# IWRL6432.net
KiCad netlist of a schematic drawn in Altium Designer
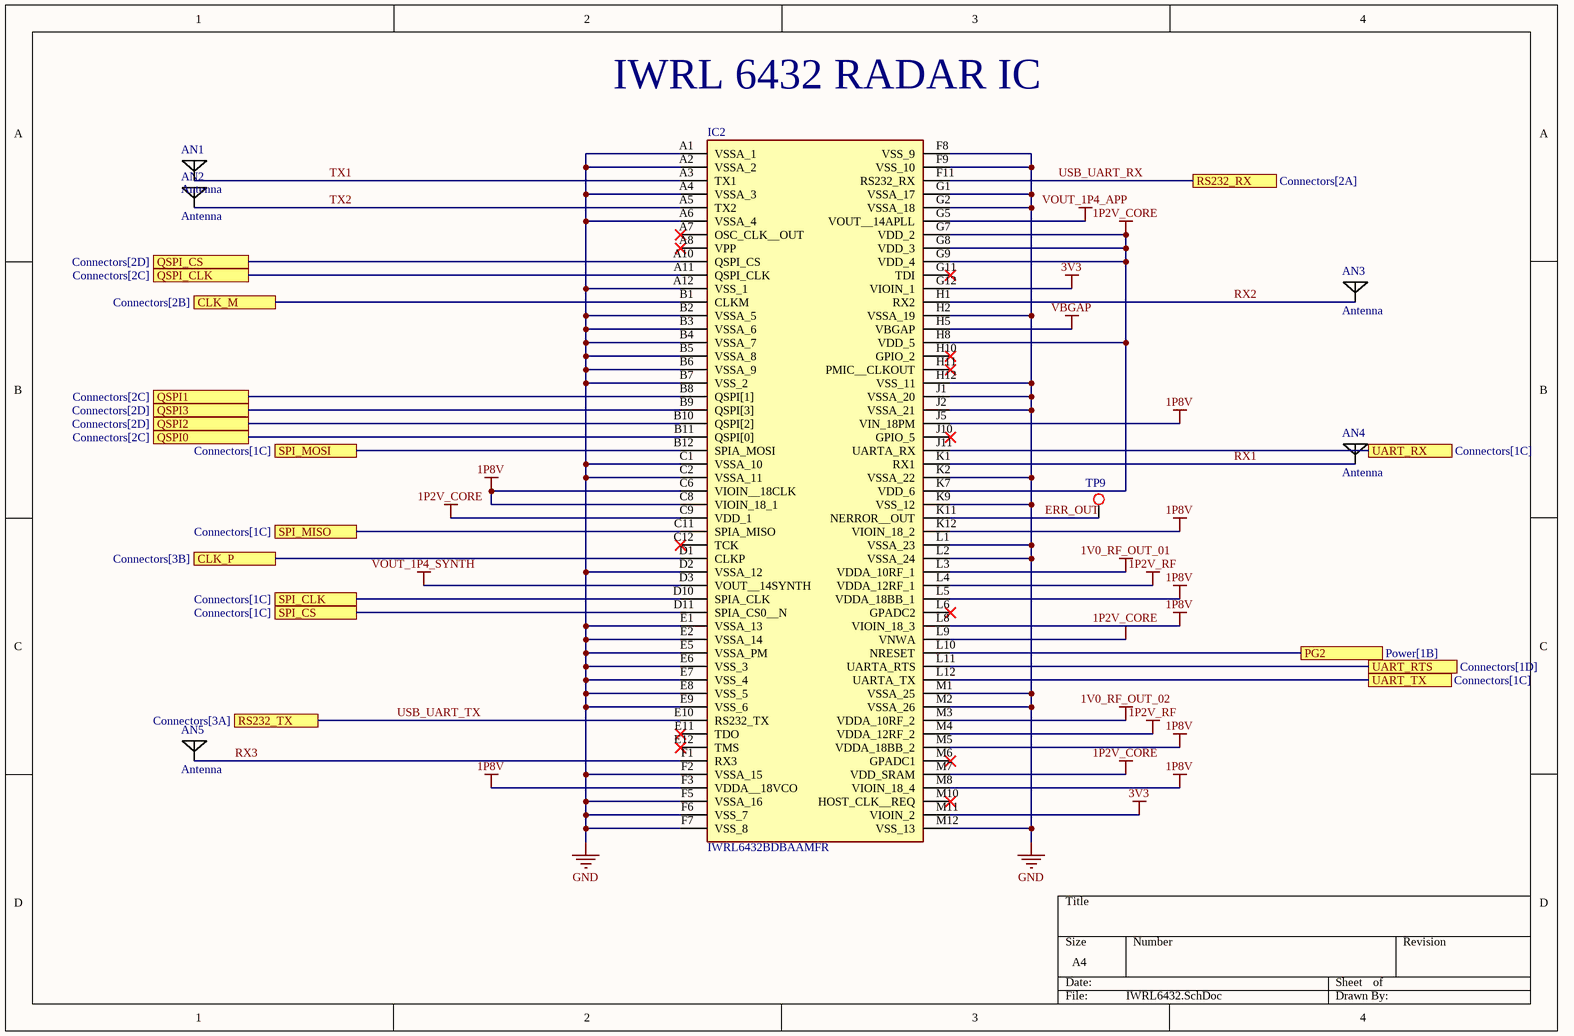
[diagram p0: IWRL6432.SchDoc]

(export (version "E")
  (design (tool "Eeschema 10.0.6"))
  (components
    (comp (ref "AN1") (value "Antenna") (footprint "Antenna") (libsource (lib "Schlib1") (part "Antenna")))
    (comp (ref "AN2") (value "Antenna") (footprint "Antenna") (libsource (lib "Schlib1") (part "Antenna")))
    (comp (ref "AN3") (value "Antenna") (footprint "Antenna") (libsource (lib "Schlib1") (part "Antenna")))
    (comp (ref "AN4") (value "Antenna") (footprint "Antenna") (libsource (lib "Schlib1") (part "Antenna")))
    (comp (ref "AN5") (value "Antenna") (footprint "Antenna") (libsource (lib "Schlib1") (part "Antenna")))
    (comp (ref "IC2")
      (value "IWRL6432BDBAAMFR")
      (footprint "SamacSys:BGA102C50P12X12_645X645X97")
      (description "Integrated Circuit")
      (libsource (lib "*") (part "IWRL6432BDBAAMFR"))
    )
    (comp (ref "TP9") (value "TP_1") (footprint "Testpoint") (libsource (lib "Schlib1") (part "Testpoint")))
  )
  (nets
    (net (code "1") (name "/CLK_M") (class "Default")
      (node (ref "IC2") (pin "B1") (pinfunction "CLKM_B1") (pintype "passive"))
    )
    (net (code "2") (name "/CLK_P") (class "Default")
      (node (ref "IC2") (pin "D1") (pinfunction "CLKP_D1") (pintype "passive"))
    )
    (net (code "3") (name "/ERR_OUT") (class "Default")
      (node (ref "IC2") (pin "K11") (pinfunction "NERROR__OUT_K11") (pintype "passive"))
      (node (ref "TP9") (pin "0") (pinfunction "0_0") (pintype "passive"))
    )
    (net (code "4") (name "/PG2") (class "Default")
      (node (ref "IC2") (pin "L10") (pinfunction "NRESET_L10") (pintype "passive"))
    )
    (net (code "5") (name "/QSPI0") (class "Default")
      (node (ref "IC2") (pin "B11") (pinfunction "QSPI[0]_B11") (pintype "passive"))
    )
    (net (code "6") (name "/QSPI1") (class "Default")
      (node (ref "IC2") (pin "B8") (pinfunction "QSPI[1]_B8") (pintype "passive"))
    )
    (net (code "7") (name "/QSPI2") (class "Default")
      (node (ref "IC2") (pin "B10") (pinfunction "QSPI[2]_B10") (pintype "passive"))
    )
    (net (code "8") (name "/QSPI3") (class "Default")
      (node (ref "IC2") (pin "B9") (pinfunction "QSPI[3]_B9") (pintype "passive"))
    )
    (net (code "9") (name "/QSPI_CLK") (class "Default")
      (node (ref "IC2") (pin "A11") (pinfunction "QSPI_CLK_A11") (pintype "passive"))
    )
    (net (code "10") (name "/QSPI_CS") (class "Default")
      (node (ref "IC2") (pin "A10") (pinfunction "QSPI_CS_A10") (pintype "passive"))
    )
    (net (code "11") (name "/RX1") (class "Default")
      (node (ref "AN4") (pin "0") (pinfunction "0_0") (pintype "passive"))
      (node (ref "IC2") (pin "K1") (pinfunction "RX1_K1") (pintype "passive"))
    )
    (net (code "12") (name "/RX2") (class "Default")
      (node (ref "AN3") (pin "0") (pinfunction "0_0") (pintype "passive"))
      (node (ref "IC2") (pin "H1") (pinfunction "RX2_H1") (pintype "passive"))
    )
    (net (code "13") (name "/RX3") (class "Default")
      (node (ref "AN5") (pin "0") (pinfunction "0_0") (pintype "passive"))
      (node (ref "IC2") (pin "F1") (pinfunction "RX3_F1") (pintype "passive"))
    )
    (net (code "14") (name "/SPI_CLK") (class "Default")
      (node (ref "IC2") (pin "D10") (pinfunction "SPIA_CLK_D10") (pintype "passive"))
    )
    (net (code "15") (name "/SPI_CS") (class "Default")
      (node (ref "IC2") (pin "D11") (pinfunction "SPIA_CS0__N_D11") (pintype "passive"))
    )
    (net (code "16") (name "/SPI_MISO") (class "Default")
      (node (ref "IC2") (pin "C11") (pinfunction "SPIA_MISO_C11") (pintype "passive"))
    )
    (net (code "17") (name "/SPI_MOSI") (class "Default")
      (node (ref "IC2") (pin "B12") (pinfunction "SPIA_MOSI_B12") (pintype "passive"))
    )
    (net (code "18") (name "/TX1") (class "Default")
      (node (ref "AN1") (pin "0") (pinfunction "0_0") (pintype "passive"))
      (node (ref "IC2") (pin "A3") (pinfunction "TX1_A3") (pintype "passive"))
    )
    (net (code "19") (name "/TX2") (class "Default")
      (node (ref "AN2") (pin "0") (pinfunction "0_0") (pintype "passive"))
      (node (ref "IC2") (pin "A5") (pinfunction "TX2_A5") (pintype "passive"))
    )
    (net (code "20") (name "/UART_RTS") (class "Default")
      (node (ref "IC2") (pin "L11") (pinfunction "UARTA_RTS_L11") (pintype "passive"))
    )
    (net (code "21") (name "/UART_RX") (class "Default")
      (node (ref "IC2") (pin "J11") (pinfunction "UARTA_RX_J11") (pintype "passive"))
    )
    (net (code "22") (name "/UART_TX") (class "Default")
      (node (ref "IC2") (pin "L12") (pinfunction "UARTA_TX_L12") (pintype "passive"))
    )
    (net (code "23") (name "/USB_UART_RX") (class "Default")
      (node (ref "IC2") (pin "F11") (pinfunction "RS232_RX_F11") (pintype "passive"))
    )
    (net (code "24") (name "/USB_UART_TX") (class "Default")
      (node (ref "IC2") (pin "E10") (pinfunction "RS232_TX_E10") (pintype "passive"))
    )
    (net (code "25") (name "1P2V_CORE") (class "Default")
      (node (ref "IC2") (pin "C9") (pinfunction "VDD_1_C9") (pintype "passive"))
      (node (ref "IC2") (pin "G7") (pinfunction "VDD_2_G7") (pintype "passive"))
      (node (ref "IC2") (pin "G8") (pinfunction "VDD_3_G8") (pintype "passive"))
      (node (ref "IC2") (pin "G9") (pinfunction "VDD_4_G9") (pintype "passive"))
      (node (ref "IC2") (pin "H8") (pinfunction "VDD_5_H8") (pintype "passive"))
      (node (ref "IC2") (pin "K7") (pinfunction "VDD_6_K7") (pintype "passive"))
      (node (ref "IC2") (pin "L9") (pinfunction "VNWA_L9") (pintype "passive"))
      (node (ref "IC2") (pin "M7") (pinfunction "VDD_SRAM_M7") (pintype "passive"))
    )
    (net (code "26") (name "1P2V_RF") (class "Default")
      (node (ref "IC2") (pin "L4") (pinfunction "VDDA_12RF_1_L4") (pintype "passive"))
      (node (ref "IC2") (pin "M4") (pinfunction "VDDA_12RF_2_M4") (pintype "passive"))
    )
    (net (code "27") (name "1P8V") (class "Default")
      (node (ref "IC2") (pin "C6") (pinfunction "VIOIN__18CLK_C6") (pintype "passive"))
      (node (ref "IC2") (pin "C8") (pinfunction "VIOIN_18_1_C8") (pintype "passive"))
      (node (ref "IC2") (pin "F3") (pinfunction "VDDA__18VCO_F3") (pintype "passive"))
      (node (ref "IC2") (pin "J5") (pinfunction "VIN_18PM_J5") (pintype "passive"))
      (node (ref "IC2") (pin "K12") (pinfunction "VIOIN_18_2_K12") (pintype "passive"))
      (node (ref "IC2") (pin "L5") (pinfunction "VDDA_18BB_1_L5") (pintype "passive"))
      (node (ref "IC2") (pin "L8") (pinfunction "VIOIN_18_3_L8") (pintype "passive"))
      (node (ref "IC2") (pin "M5") (pinfunction "VDDA_18BB_2_M5") (pintype "passive"))
      (node (ref "IC2") (pin "M8") (pinfunction "VIOIN_18_4_M8") (pintype "passive"))
    )
    (net (code "28") (name "1V0_RF_OUT_01") (class "Default")
      (node (ref "IC2") (pin "L3") (pinfunction "VDDA_10RF_1_L3") (pintype "passive"))
    )
    (net (code "29") (name "1V0_RF_OUT_02") (class "Default")
      (node (ref "IC2") (pin "M3") (pinfunction "VDDA_10RF_2_M3") (pintype "passive"))
    )
    (net (code "30") (name "3V3") (class "Default")
      (node (ref "IC2") (pin "G12") (pinfunction "VIOIN_1_G12") (pintype "passive"))
      (node (ref "IC2") (pin "M11") (pinfunction "VIOIN_2_M11") (pintype "passive"))
    )
    (net (code "31") (name "GND") (class "Default")
      (node (ref "IC2") (pin "A1") (pinfunction "VSSA_1_A1") (pintype "passive"))
      (node (ref "IC2") (pin "A12") (pinfunction "VSS_1_A12") (pintype "passive"))
      (node (ref "IC2") (pin "A2") (pinfunction "VSSA_2_A2") (pintype "passive"))
      (node (ref "IC2") (pin "A4") (pinfunction "VSSA_3_A4") (pintype "passive"))
      (node (ref "IC2") (pin "A6") (pinfunction "VSSA_4_A6") (pintype "passive"))
      (node (ref "IC2") (pin "B2") (pinfunction "VSSA_5_B2") (pintype "passive"))
      (node (ref "IC2") (pin "B3") (pinfunction "VSSA_6_B3") (pintype "passive"))
      (node (ref "IC2") (pin "B4") (pinfunction "VSSA_7_B4") (pintype "passive"))
      (node (ref "IC2") (pin "B5") (pinfunction "VSSA_8_B5") (pintype "passive"))
      (node (ref "IC2") (pin "B6") (pinfunction "VSSA_9_B6") (pintype "passive"))
      (node (ref "IC2") (pin "B7") (pinfunction "VSS_2_B7") (pintype "passive"))
      (node (ref "IC2") (pin "C1") (pinfunction "VSSA_10_C1") (pintype "passive"))
      (node (ref "IC2") (pin "C2") (pinfunction "VSSA_11_C2") (pintype "passive"))
      (node (ref "IC2") (pin "D2") (pinfunction "VSSA_12_D2") (pintype "passive"))
      (node (ref "IC2") (pin "E1") (pinfunction "VSSA_13_E1") (pintype "passive"))
      (node (ref "IC2") (pin "E2") (pinfunction "VSSA_14_E2") (pintype "passive"))
      (node (ref "IC2") (pin "E5") (pinfunction "VSSA_PM_E5") (pintype "passive"))
      (node (ref "IC2") (pin "E6") (pinfunction "VSS_3_E6") (pintype "passive"))
      (node (ref "IC2") (pin "E7") (pinfunction "VSS_4_E7") (pintype "passive"))
      (node (ref "IC2") (pin "E8") (pinfunction "VSS_5_E8") (pintype "passive"))
      (node (ref "IC2") (pin "E9") (pinfunction "VSS_6_E9") (pintype "passive"))
      (node (ref "IC2") (pin "F2") (pinfunction "VSSA_15_F2") (pintype "passive"))
      (node (ref "IC2") (pin "F5") (pinfunction "VSSA_16_F5") (pintype "passive"))
      (node (ref "IC2") (pin "F6") (pinfunction "VSS_7_F6") (pintype "passive"))
      (node (ref "IC2") (pin "F7") (pinfunction "VSS_8_F7") (pintype "passive"))
      (node (ref "IC2") (pin "F8") (pinfunction "VSS_9_F8") (pintype "passive"))
      (node (ref "IC2") (pin "F9") (pinfunction "VSS_10_F9") (pintype "passive"))
      (node (ref "IC2") (pin "G1") (pinfunction "VSSA_17_G1") (pintype "passive"))
      (node (ref "IC2") (pin "G2") (pinfunction "VSSA_18_G2") (pintype "passive"))
      (node (ref "IC2") (pin "H12") (pinfunction "VSS_11_H12") (pintype "passive"))
      (node (ref "IC2") (pin "H2") (pinfunction "VSSA_19_H2") (pintype "passive"))
      (node (ref "IC2") (pin "J1") (pinfunction "VSSA_20_J1") (pintype "passive"))
      (node (ref "IC2") (pin "J2") (pinfunction "VSSA_21_J2") (pintype "passive"))
      (node (ref "IC2") (pin "K2") (pinfunction "VSSA_22_K2") (pintype "passive"))
      (node (ref "IC2") (pin "K9") (pinfunction "VSS_12_K9") (pintype "passive"))
      (node (ref "IC2") (pin "L1") (pinfunction "VSSA_23_L1") (pintype "passive"))
      (node (ref "IC2") (pin "L2") (pinfunction "VSSA_24_L2") (pintype "passive"))
      (node (ref "IC2") (pin "M1") (pinfunction "VSSA_25_M1") (pintype "passive"))
      (node (ref "IC2") (pin "M12") (pinfunction "VSS_13_M12") (pintype "passive"))
      (node (ref "IC2") (pin "M2") (pinfunction "VSSA_26_M2") (pintype "passive"))
    )
    (net (code "32") (name "VBGAP") (class "Default")
      (node (ref "IC2") (pin "H5") (pinfunction "VBGAP_H5") (pintype "passive"))
    )
    (net (code "33") (name "VOUT_1P4_APP") (class "Default")
      (node (ref "IC2") (pin "G5") (pinfunction "VOUT__14APLL_G5") (pintype "passive"))
    )
    (net (code "34") (name "VOUT_1P4_SYNTH") (class "Default")
      (node (ref "IC2") (pin "D3") (pinfunction "VOUT__14SYNTH_D3") (pintype "passive"))
    )
    (net (code "35") (name "unconnected-(IC2-GPADC1-PadM6)") (class "Default")
      (node (ref "IC2") (pin "M6") (pinfunction "GPADC1_M6") (pintype "passive+no_connect"))
    )
    (net (code "36") (name "unconnected-(IC2-GPADC2-PadL6)") (class "Default")
      (node (ref "IC2") (pin "L6") (pinfunction "GPADC2_L6") (pintype "passive+no_connect"))
    )
    (net (code "37") (name "unconnected-(IC2-GPIO_2-PadH10)") (class "Default")
      (node (ref "IC2") (pin "H10") (pinfunction "GPIO_2_H10") (pintype "passive+no_connect"))
    )
    (net (code "38") (name "unconnected-(IC2-GPIO_5-PadJ10)") (class "Default")
      (node (ref "IC2") (pin "J10") (pinfunction "GPIO_5_J10") (pintype "passive+no_connect"))
    )
    (net (code "39") (name "unconnected-(IC2-HOST_CLK__REQ-PadM10)") (class "Default")
      (node (ref "IC2") (pin "M10") (pinfunction "HOST_CLK__REQ_M10") (pintype "passive+no_connect"))
    )
    (net (code "40") (name "unconnected-(IC2-OSC_CLK__OUT-PadA7)") (class "Default")
      (node (ref "IC2") (pin "A7") (pinfunction "OSC_CLK__OUT_A7") (pintype "passive+no_connect"))
    )
    (net (code "41") (name "unconnected-(IC2-PMIC__CLKOUT-PadH11)") (class "Default")
      (node (ref "IC2") (pin "H11") (pinfunction "PMIC__CLKOUT_H11") (pintype "passive+no_connect"))
    )
    (net (code "42") (name "unconnected-(IC2-TCK-PadC12)") (class "Default")
      (node (ref "IC2") (pin "C12") (pinfunction "TCK_C12") (pintype "passive+no_connect"))
    )
    (net (code "43") (name "unconnected-(IC2-TDI-PadG11)") (class "Default")
      (node (ref "IC2") (pin "G11") (pinfunction "TDI_G11") (pintype "passive+no_connect"))
    )
    (net (code "44") (name "unconnected-(IC2-TDO-PadE11)") (class "Default")
      (node (ref "IC2") (pin "E11") (pinfunction "TDO_E11") (pintype "passive+no_connect"))
    )
    (net (code "45") (name "unconnected-(IC2-TMS-PadE12)") (class "Default")
      (node (ref "IC2") (pin "E12") (pinfunction "TMS_E12") (pintype "passive+no_connect"))
    )
    (net (code "46") (name "unconnected-(IC2-VPP-PadA8)") (class "Default")
      (node (ref "IC2") (pin "A8") (pinfunction "VPP_A8") (pintype "passive+no_connect"))
    )
  )
)
